# BluetoothModulePCBv2.net
KiCad netlist of a schematic drawn in EAGLE
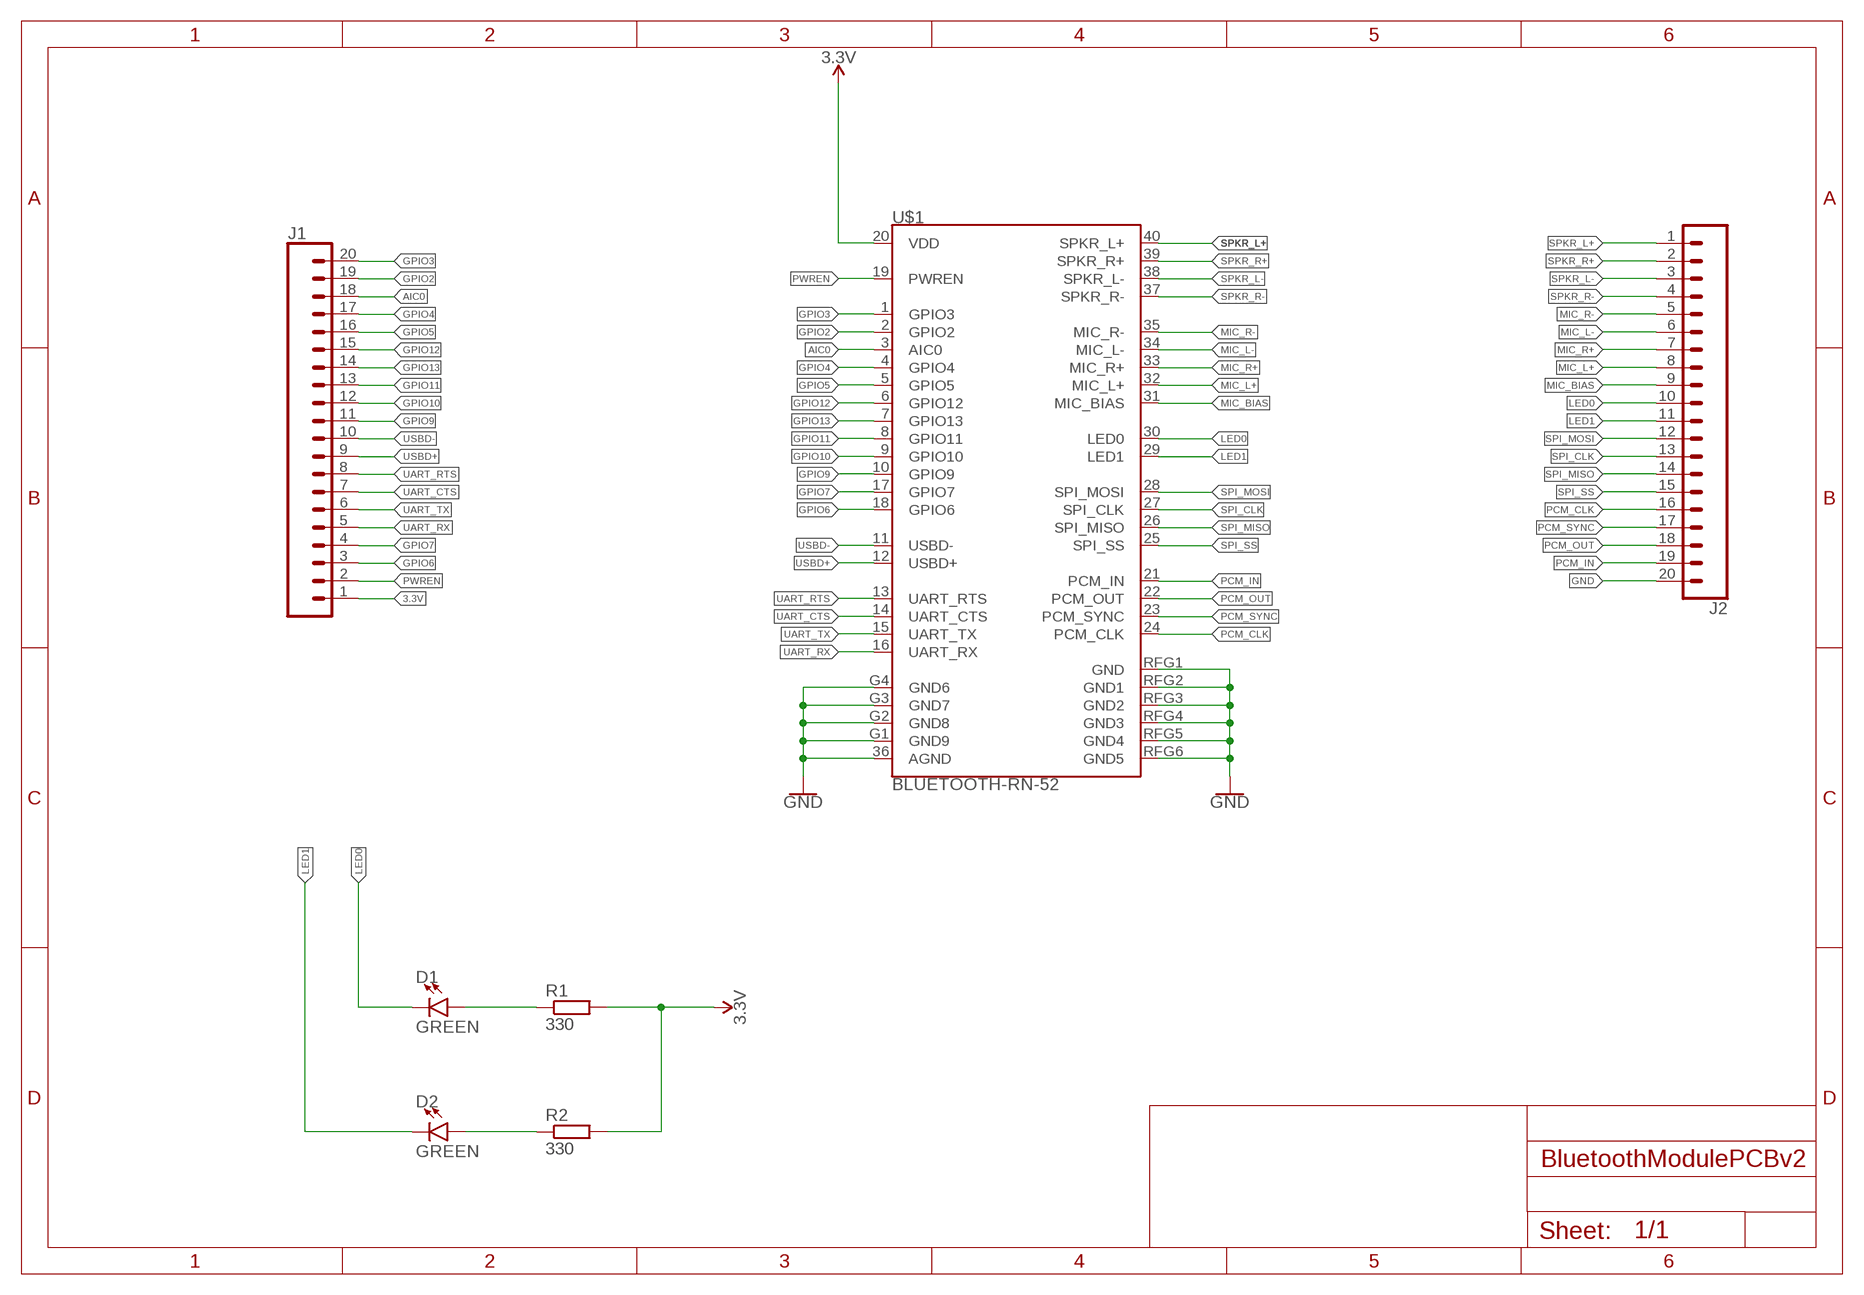
[diagram p0: schematic, sheet 1]

(export (version "E")
  (design (tool "Eeschema 10.0.6"))
  (components
    (comp (ref "D1")
      (value "GREEN")
      (footprint "eagle-import:LED_3MM")
      (libsource (lib "eagle-import") (part "LED3MM"))
    )
    (comp (ref "D2")
      (value "GREEN")
      (footprint "eagle-import:LED_3MM")
      (libsource (lib "eagle-import") (part "LED3MM"))
    )
    (comp (ref "J1")
      (value "CONN_20")
      (footprint "eagle-import:1X20")
      (libsource (lib "eagle-import") (part "CONN_20"))
    )
    (comp (ref "J2")
      (value "CONN_20")
      (footprint "eagle-import:1X20")
      (libsource (lib "eagle-import") (part "CONN_20"))
    )
    (comp (ref "R1")
      (value "330")
      (footprint "eagle-import:0204_7")
      (libsource (lib "eagle-import") (part "R-EU_0204/7"))
    )
    (comp (ref "R2")
      (value "330")
      (footprint "eagle-import:0204_7")
      (libsource (lib "eagle-import") (part "R-EU_0204/7"))
    )
    (comp (ref "U$1")
      (value "BLUETOOTH-RN-52")
      (footprint "eagle-import:RN-52")
      (libsource (lib "eagle-import") (part "BLUETOOTH-RN-52"))
    )
  )
  (nets
    (net (code "1") (name "3.3V") (class "Default")
      (node (ref "J1") (pin "1") (pinfunction "1_1") (pintype "passive"))
      (node (ref "R1") (pin "2") (pinfunction "2_2") (pintype "passive"))
      (node (ref "R2") (pin "2") (pinfunction "2_2") (pintype "passive"))
      (node (ref "U$1") (pin "20") (pinfunction "VDD_20") (pintype "bidirectional"))
    )
    (net (code "2") (name "AIC0") (class "Default")
      (node (ref "J1") (pin "18") (pinfunction "18_18") (pintype "passive"))
      (node (ref "U$1") (pin "3") (pinfunction "AIC0_3") (pintype "bidirectional"))
    )
    (net (code "3") (name "GND") (class "Default")
      (node (ref "J2") (pin "20") (pinfunction "20_20") (pintype "passive"))
      (node (ref "U$1") (pin "36") (pinfunction "AGND_36") (pintype "bidirectional"))
      (node (ref "U$1") (pin "G1") (pinfunction "GND9_G1") (pintype "bidirectional"))
      (node (ref "U$1") (pin "G2") (pinfunction "GND8_G2") (pintype "bidirectional"))
      (node (ref "U$1") (pin "G3") (pinfunction "GND7_G3") (pintype "bidirectional"))
      (node (ref "U$1") (pin "G4") (pinfunction "GND6_G4") (pintype "bidirectional"))
      (node (ref "U$1") (pin "RFG1") (pinfunction "GND_RFG1") (pintype "bidirectional"))
      (node (ref "U$1") (pin "RFG2") (pinfunction "GND1_RFG2") (pintype "bidirectional"))
      (node (ref "U$1") (pin "RFG3") (pinfunction "GND2_RFG3") (pintype "bidirectional"))
      (node (ref "U$1") (pin "RFG4") (pinfunction "GND3_RFG4") (pintype "bidirectional"))
      (node (ref "U$1") (pin "RFG5") (pinfunction "GND4_RFG5") (pintype "bidirectional"))
      (node (ref "U$1") (pin "RFG6") (pinfunction "GND5_RFG6") (pintype "bidirectional"))
    )
    (net (code "4") (name "GPIO2") (class "Default")
      (node (ref "J1") (pin "19") (pinfunction "19_19") (pintype "passive"))
      (node (ref "U$1") (pin "2") (pinfunction "GPIO2_2") (pintype "bidirectional"))
    )
    (net (code "5") (name "GPIO3") (class "Default")
      (node (ref "J1") (pin "20") (pinfunction "20_20") (pintype "passive"))
      (node (ref "U$1") (pin "1") (pinfunction "GPIO3_1") (pintype "bidirectional"))
    )
    (net (code "6") (name "GPIO4") (class "Default")
      (node (ref "J1") (pin "17") (pinfunction "17_17") (pintype "passive"))
      (node (ref "U$1") (pin "4") (pinfunction "GPIO4_4") (pintype "bidirectional"))
    )
    (net (code "7") (name "GPIO5") (class "Default")
      (node (ref "J1") (pin "16") (pinfunction "16_16") (pintype "passive"))
      (node (ref "U$1") (pin "5") (pinfunction "GPIO5_5") (pintype "bidirectional"))
    )
    (net (code "8") (name "GPIO6") (class "Default")
      (node (ref "J1") (pin "3") (pinfunction "3_3") (pintype "passive"))
      (node (ref "U$1") (pin "18") (pinfunction "GPIO6_18") (pintype "bidirectional"))
    )
    (net (code "9") (name "GPIO7") (class "Default")
      (node (ref "J1") (pin "4") (pinfunction "4_4") (pintype "passive"))
      (node (ref "U$1") (pin "17") (pinfunction "GPIO7_17") (pintype "bidirectional"))
    )
    (net (code "10") (name "GPIO9") (class "Default")
      (node (ref "J1") (pin "11") (pinfunction "11_11") (pintype "passive"))
      (node (ref "U$1") (pin "10") (pinfunction "GPIO9_10") (pintype "bidirectional"))
    )
    (net (code "11") (name "GPIO10") (class "Default")
      (node (ref "J1") (pin "12") (pinfunction "12_12") (pintype "passive"))
      (node (ref "U$1") (pin "9") (pinfunction "GPIO10_9") (pintype "bidirectional"))
    )
    (net (code "12") (name "GPIO11") (class "Default")
      (node (ref "J1") (pin "13") (pinfunction "13_13") (pintype "passive"))
      (node (ref "U$1") (pin "8") (pinfunction "GPIO11_8") (pintype "bidirectional"))
    )
    (net (code "13") (name "GPIO12") (class "Default")
      (node (ref "J1") (pin "15") (pinfunction "15_15") (pintype "passive"))
      (node (ref "U$1") (pin "6") (pinfunction "GPIO12_6") (pintype "bidirectional"))
    )
    (net (code "14") (name "GPIO13") (class "Default")
      (node (ref "J1") (pin "14") (pinfunction "14_14") (pintype "passive"))
      (node (ref "U$1") (pin "7") (pinfunction "GPIO13_7") (pintype "bidirectional"))
    )
    (net (code "15") (name "LED0") (class "Default")
      (node (ref "D1") (pin "K") (pinfunction "C_K") (pintype "passive"))
      (node (ref "J2") (pin "10") (pinfunction "10_10") (pintype "passive"))
      (node (ref "U$1") (pin "30") (pinfunction "LED0_30") (pintype "bidirectional"))
    )
    (net (code "16") (name "LED1") (class "Default")
      (node (ref "D2") (pin "K") (pinfunction "C_K") (pintype "passive"))
      (node (ref "J2") (pin "11") (pinfunction "11_11") (pintype "passive"))
      (node (ref "U$1") (pin "29") (pinfunction "LED1_29") (pintype "bidirectional"))
    )
    (net (code "17") (name "MIC_BIAS") (class "Default")
      (node (ref "J2") (pin "9") (pinfunction "9_9") (pintype "passive"))
      (node (ref "U$1") (pin "31") (pinfunction "MIC_BIAS_31") (pintype "bidirectional"))
    )
    (net (code "18") (name "MIC_L+") (class "Default")
      (node (ref "J2") (pin "8") (pinfunction "8_8") (pintype "passive"))
      (node (ref "U$1") (pin "32") (pinfunction "MIC_L+_32") (pintype "bidirectional"))
    )
    (net (code "19") (name "MIC_L-") (class "Default")
      (node (ref "J2") (pin "6") (pinfunction "6_6") (pintype "passive"))
      (node (ref "U$1") (pin "34") (pinfunction "MIC_L-_34") (pintype "bidirectional"))
    )
    (net (code "20") (name "MIC_R+") (class "Default")
      (node (ref "J2") (pin "7") (pinfunction "7_7") (pintype "passive"))
      (node (ref "U$1") (pin "33") (pinfunction "MIC_R+_33") (pintype "bidirectional"))
    )
    (net (code "21") (name "MIC_R-") (class "Default")
      (node (ref "J2") (pin "5") (pinfunction "5_5") (pintype "passive"))
      (node (ref "U$1") (pin "35") (pinfunction "MIC_R-_35") (pintype "bidirectional"))
    )
    (net (code "22") (name "Net-(D1-PadA)") (class "Default")
      (node (ref "D1") (pin "A") (pinfunction "A_A") (pintype "passive"))
      (node (ref "R1") (pin "1") (pinfunction "1_1") (pintype "passive"))
    )
    (net (code "23") (name "Net-(D2-PadA)") (class "Default")
      (node (ref "D2") (pin "A") (pinfunction "A_A") (pintype "passive"))
      (node (ref "R2") (pin "1") (pinfunction "1_1") (pintype "passive"))
    )
    (net (code "24") (name "PCM_CLK") (class "Default")
      (node (ref "J2") (pin "16") (pinfunction "16_16") (pintype "passive"))
      (node (ref "U$1") (pin "24") (pinfunction "PCM_CLK_24") (pintype "bidirectional"))
    )
    (net (code "25") (name "PCM_IN") (class "Default")
      (node (ref "J2") (pin "19") (pinfunction "19_19") (pintype "passive"))
      (node (ref "U$1") (pin "21") (pinfunction "PCM_IN_21") (pintype "bidirectional"))
    )
    (net (code "26") (name "PCM_OUT") (class "Default")
      (node (ref "J2") (pin "18") (pinfunction "18_18") (pintype "passive"))
      (node (ref "U$1") (pin "22") (pinfunction "PCM_OUT_22") (pintype "bidirectional"))
    )
    (net (code "27") (name "PCM_SYNC") (class "Default")
      (node (ref "J2") (pin "17") (pinfunction "17_17") (pintype "passive"))
      (node (ref "U$1") (pin "23") (pinfunction "PCM_SYNC_23") (pintype "bidirectional"))
    )
    (net (code "28") (name "PWREN") (class "Default")
      (node (ref "J1") (pin "2") (pinfunction "2_2") (pintype "passive"))
      (node (ref "U$1") (pin "19") (pinfunction "PWREN_19") (pintype "bidirectional"))
    )
    (net (code "29") (name "SPI_CLK") (class "Default")
      (node (ref "J2") (pin "13") (pinfunction "13_13") (pintype "passive"))
      (node (ref "U$1") (pin "27") (pinfunction "SPI_CLK_27") (pintype "bidirectional"))
    )
    (net (code "30") (name "SPI_MISO") (class "Default")
      (node (ref "J2") (pin "14") (pinfunction "14_14") (pintype "passive"))
      (node (ref "U$1") (pin "26") (pinfunction "SPI_MISO_26") (pintype "bidirectional"))
    )
    (net (code "31") (name "SPI_MOSI") (class "Default")
      (node (ref "J2") (pin "12") (pinfunction "12_12") (pintype "passive"))
      (node (ref "U$1") (pin "28") (pinfunction "SPI_MOSI_28") (pintype "bidirectional"))
    )
    (net (code "32") (name "SPI_SS") (class "Default")
      (node (ref "J2") (pin "15") (pinfunction "15_15") (pintype "passive"))
      (node (ref "U$1") (pin "25") (pinfunction "SPI_SS_25") (pintype "bidirectional"))
    )
    (net (code "33") (name "SPKR_L+") (class "Default")
      (node (ref "J2") (pin "1") (pinfunction "1_1") (pintype "passive"))
      (node (ref "U$1") (pin "40") (pinfunction "SPKR_L+_40") (pintype "bidirectional"))
    )
    (net (code "34") (name "SPKR_L-") (class "Default")
      (node (ref "J2") (pin "3") (pinfunction "3_3") (pintype "passive"))
      (node (ref "U$1") (pin "38") (pinfunction "SPKR_L-_38") (pintype "bidirectional"))
    )
    (net (code "35") (name "SPKR_R+") (class "Default")
      (node (ref "J2") (pin "2") (pinfunction "2_2") (pintype "passive"))
      (node (ref "U$1") (pin "39") (pinfunction "SPKR_R+_39") (pintype "bidirectional"))
    )
    (net (code "36") (name "SPKR_R-") (class "Default")
      (node (ref "J2") (pin "4") (pinfunction "4_4") (pintype "passive"))
      (node (ref "U$1") (pin "37") (pinfunction "SPKR_R-_37") (pintype "bidirectional"))
    )
    (net (code "37") (name "UART_CTS") (class "Default")
      (node (ref "J1") (pin "7") (pinfunction "7_7") (pintype "passive"))
      (node (ref "U$1") (pin "14") (pinfunction "UART_CTS_14") (pintype "bidirectional"))
    )
    (net (code "38") (name "UART_RTS") (class "Default")
      (node (ref "J1") (pin "8") (pinfunction "8_8") (pintype "passive"))
      (node (ref "U$1") (pin "13") (pinfunction "UART_RTS_13") (pintype "bidirectional"))
    )
    (net (code "39") (name "UART_RX") (class "Default")
      (node (ref "J1") (pin "5") (pinfunction "5_5") (pintype "passive"))
      (node (ref "U$1") (pin "16") (pinfunction "UART_RX_16") (pintype "bidirectional"))
    )
    (net (code "40") (name "UART_TX") (class "Default")
      (node (ref "J1") (pin "6") (pinfunction "6_6") (pintype "passive"))
      (node (ref "U$1") (pin "15") (pinfunction "UART_TX_15") (pintype "bidirectional"))
    )
    (net (code "41") (name "USBD+") (class "Default")
      (node (ref "J1") (pin "9") (pinfunction "9_9") (pintype "passive"))
      (node (ref "U$1") (pin "12") (pinfunction "USBD+_12") (pintype "bidirectional"))
    )
    (net (code "42") (name "USBD-") (class "Default")
      (node (ref "J1") (pin "10") (pinfunction "10_10") (pintype "passive"))
      (node (ref "U$1") (pin "11") (pinfunction "USBD-_11") (pintype "bidirectional"))
    )
  )
)
